# Pi_HDMI.net
KiCad netlist of a schematic drawn in Altium Designer
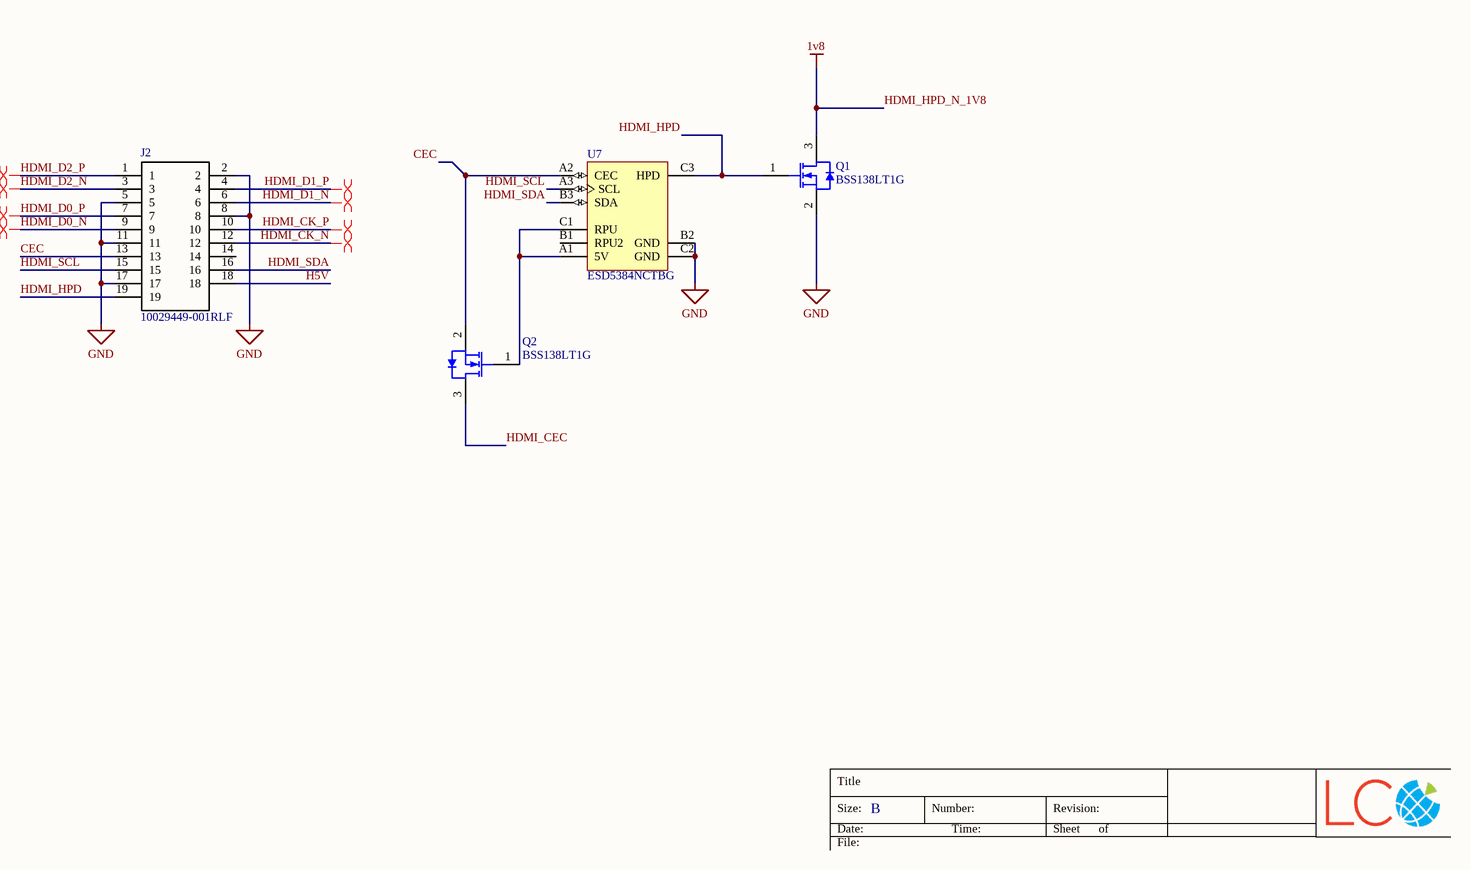
[diagram p0: Pi_HDMI.SchDoc]

(export (version "E")
  (design (tool "Eeschema 10.0.6"))
  (components
    (comp (ref "J2")
      (value "10029449-001RLF")
      (footprint "SamacSys:10029449-001RLF_FCI")
      (description "Connector")
      (fields
        (field (name "MOUSER PART NUMBER") "649-10029449-001RLF")
        (field (name "RS PART NUMBER") "1621999")
      )
      (libsource (lib "*") (part "10029449-001RLF"))
    )
    (comp (ref "Q1")
      (value "BSS138LT1G")
      (footprint "ONSC-SOT-23-3-318-08_V")
      (description "Power MOSFET, 200 mA, 50 V, N-Channel, 3-Pin SOT-23, Pb-Free, Tape and Reel")
      (fields (field (name "MANUFACTURER") "On Semiconductor"))
      (libsource (lib "Altium Content Vault") (part "ONSC-NMOS-G1S2D3-3"))
    )
    (comp (ref "Q2")
      (value "BSS138LT1G")
      (footprint "ONSC-SOT-23-3-318-08_V")
      (description "Power MOSFET, 200 mA, 50 V, N-Channel, 3-Pin SOT-23, Pb-Free, Tape and Reel")
      (fields (field (name "MANUFACTURER") "On Semiconductor"))
      (libsource (lib "Altium Content Vault") (part "ONSC-NMOS-G1S2D3-3"))
    )
    (comp (ref "U7")
      (value "ESD5384NCTBG")
      (footprint "ONSC-WLCSP-9-567CX-01")
      (description "5-Line HDMI Control Line, ESD Protection, 9-Pin WLCSP, Pb-Free, Tape and Reel")
      (fields (field (name "MANUFACTURER") "On Semiconductor"))
      (libsource (lib "Altium Content Vault") (part "ONSC-ESD5384-WLCSP-9-567CX-01"))
    )
  )
  (nets
    (net (code "1") (name "/CEC") (class "Default")
      (node (ref "J2") (pin "13") (pinfunction "13_13") (pintype "passive"))
      (node (ref "Q2") (pin "2") (pinfunction "S_2") (pintype "passive"))
      (node (ref "U7") (pin "A2") (pinfunction "CEC_A2") (pintype "bidirectional"))
    )
    (net (code "2") (name "/H5V") (class "Default")
      (node (ref "J2") (pin "18") (pinfunction "18_18") (pintype "passive"))
    )
    (net (code "3") (name "/HDMI_CEC") (class "Default")
      (node (ref "Q2") (pin "3") (pinfunction "D_3") (pintype "passive"))
    )
    (net (code "4") (name "/HDMI_CK_N") (class "Default")
      (node (ref "J2") (pin "12") (pinfunction "12_12") (pintype "passive"))
    )
    (net (code "5") (name "/HDMI_CK_P") (class "Default")
      (node (ref "J2") (pin "10") (pinfunction "10_10") (pintype "passive"))
    )
    (net (code "6") (name "/HDMI_D0_N") (class "Default")
      (node (ref "J2") (pin "9") (pinfunction "9_9") (pintype "passive"))
    )
    (net (code "7") (name "/HDMI_D0_P") (class "Default")
      (node (ref "J2") (pin "7") (pinfunction "7_7") (pintype "passive"))
    )
    (net (code "8") (name "/HDMI_D1_N") (class "Default")
      (node (ref "J2") (pin "6") (pinfunction "6_6") (pintype "passive"))
    )
    (net (code "9") (name "/HDMI_D1_P") (class "Default")
      (node (ref "J2") (pin "4") (pinfunction "4_4") (pintype "passive"))
    )
    (net (code "10") (name "/HDMI_D2_N") (class "Default")
      (node (ref "J2") (pin "3") (pinfunction "3_3") (pintype "passive"))
    )
    (net (code "11") (name "/HDMI_D2_P") (class "Default")
      (node (ref "J2") (pin "1") (pinfunction "1_1") (pintype "passive"))
    )
    (net (code "12") (name "/HDMI_HPD") (class "Default")
      (node (ref "J2") (pin "19") (pinfunction "19_19") (pintype "passive"))
      (node (ref "Q1") (pin "1") (pinfunction "G_1") (pintype "passive"))
      (node (ref "U7") (pin "C3") (pinfunction "HPD_C3") (pintype "passive"))
    )
    (net (code "13") (name "/HDMI_SCL") (class "Default")
      (node (ref "J2") (pin "15") (pinfunction "15_15") (pintype "passive"))
      (node (ref "U7") (pin "A3") (pinfunction "SCL_A3") (pintype "bidirectional"))
    )
    (net (code "14") (name "/HDMI_SDA") (class "Default")
      (node (ref "J2") (pin "16") (pinfunction "16_16") (pintype "passive"))
      (node (ref "U7") (pin "B3") (pinfunction "SDA_B3") (pintype "bidirectional"))
    )
    (net (code "15") (name "1v8") (class "Default")
      (node (ref "Q1") (pin "3") (pinfunction "D_3") (pintype "passive"))
    )
    (net (code "16") (name "GND") (class "Default")
      (node (ref "J2") (pin "11") (pinfunction "11_11") (pintype "passive"))
      (node (ref "J2") (pin "17") (pinfunction "17_17") (pintype "passive"))
      (node (ref "J2") (pin "2") (pinfunction "2_2") (pintype "passive"))
      (node (ref "J2") (pin "5") (pinfunction "5_5") (pintype "passive"))
      (node (ref "J2") (pin "8") (pinfunction "8_8") (pintype "passive"))
      (node (ref "Q1") (pin "2") (pinfunction "S_2") (pintype "passive"))
      (node (ref "U7") (pin "B2") (pinfunction "GND_B2") (pintype "power_in"))
      (node (ref "U7") (pin "C2") (pinfunction "GND_C2") (pintype "power_in"))
    )
    (net (code "17") (name "Net-(Q2-G)") (class "Default")
      (node (ref "Q2") (pin "1") (pinfunction "G_1") (pintype "passive"))
      (node (ref "U7") (pin "A1") (pinfunction "5V_A1") (pintype "power_in"))
      (node (ref "U7") (pin "C1") (pinfunction "RPU_C1") (pintype "power_in"))
    )
    (net (code "18") (name "unconnected-(J2-Pad14)") (class "Default")
      (node (ref "J2") (pin "14") (pinfunction "14_14") (pintype "passive"))
    )
    (net (code "19") (name "unconnected-(U7-RPU2-PadB1)") (class "Default")
      (node (ref "U7") (pin "B1") (pinfunction "RPU2_B1") (pintype "power_in"))
    )
  )
)
